# E-04_CPU_PWR.net
KiCad netlist of a schematic drawn in Altium Designer
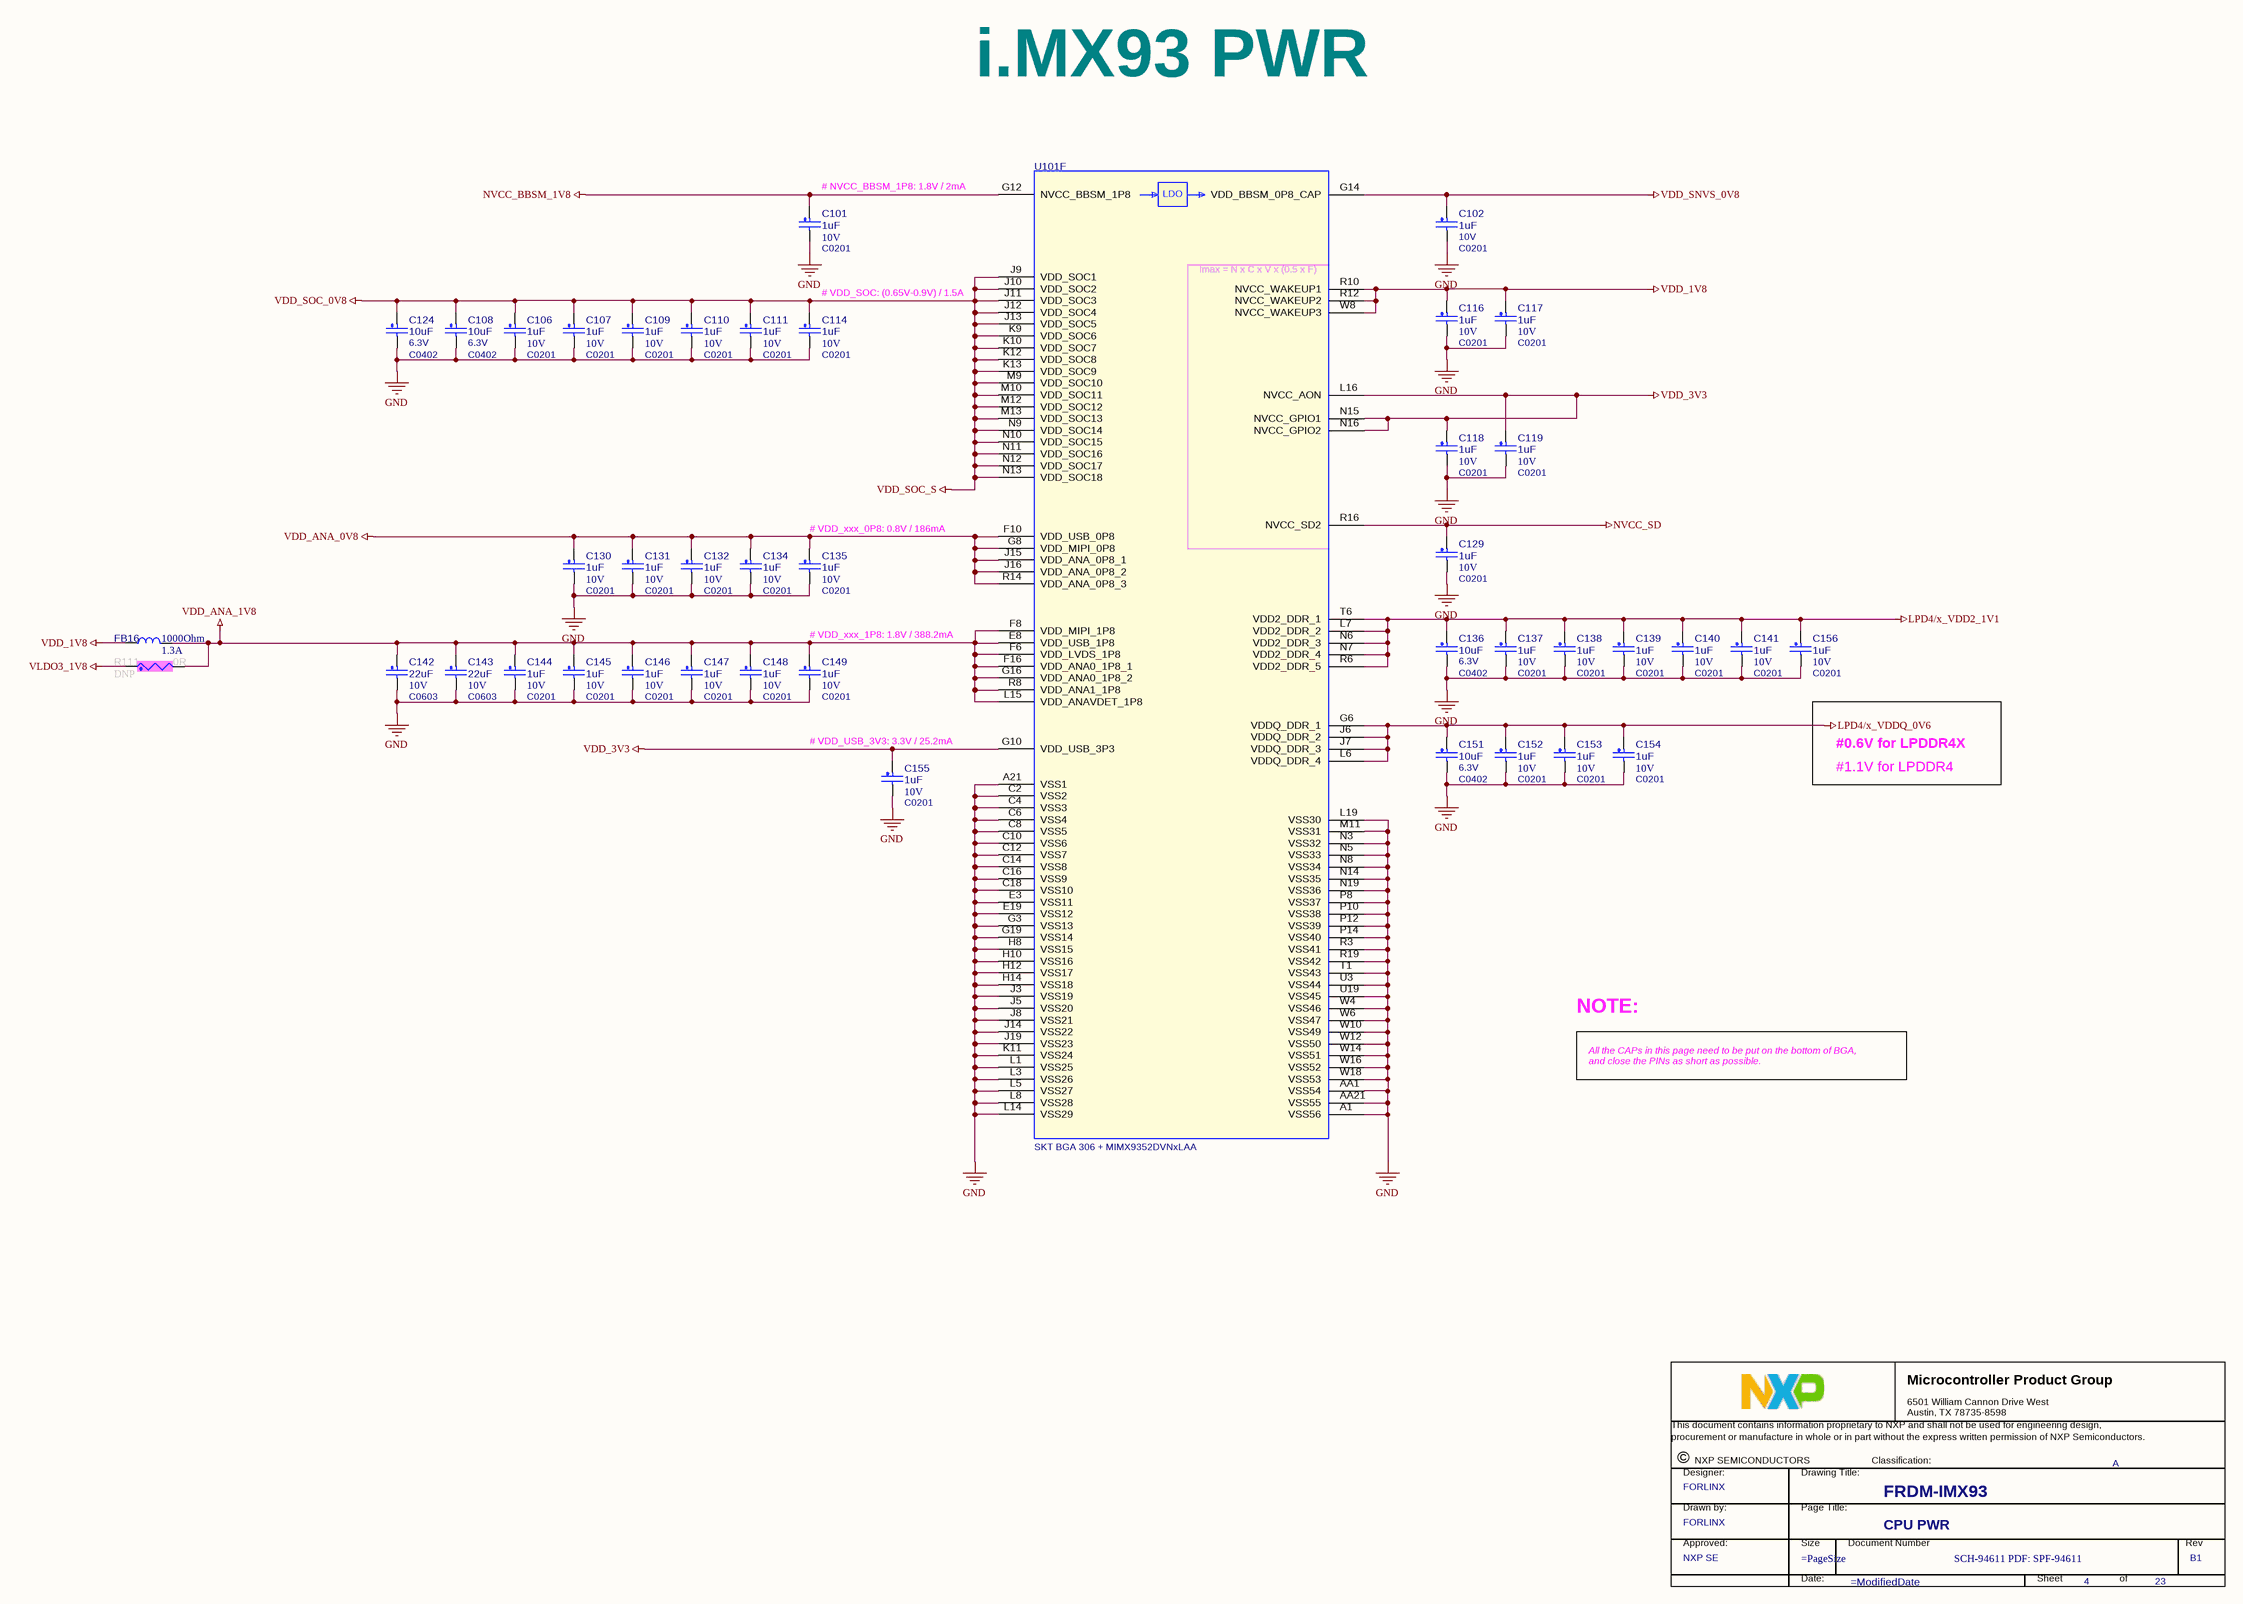
[diagram p0: E-04 CPU PWR.SchDoc]

(export (version "E")
  (design (tool "Eeschema 10.0.6"))
  (components
    (comp (ref "C101")
      (value "1uF")
      (footprint "C0201")
      (description "0201,1uF,10V,+/-20%,X5R")
      (fields
        (field (name "TOLERANCE") "10%")
        (field (name "VOLTAGE") "10V")
        (field (name "PCB FOOTPRINT") "C0201")
      )
      (libsource (lib "*") (part "CAP_NP"))
    )
    (comp (ref "C102")
      (value "1uF")
      (footprint "C0201")
      (description "0201,1uF,10V,+/-20%,X5R")
      (fields
        (field (name "VOLTAGE") "10V")
        (field (name "TOLERANCE") "20%")
        (field (name "PCB FOOTPRINT") "C0201")
      )
      (libsource (lib "*") (part "CAP_NP"))
    )
    (comp (ref "C106")
      (value "1uF")
      (footprint "C0201")
      (description "0201,1uF,10V,+/-20%,X5R")
      (fields
        (field (name "VOLTAGE") "10V")
        (field (name "TOLERANCE") "10%")
        (field (name "PCB FOOTPRINT") "C0201")
      )
      (libsource (lib "*") (part "CAP_NP"))
    )
    (comp (ref "C107")
      (value "1uF")
      (footprint "C0201")
      (description "0201,1uF,10V,+/-20%,X5R")
      (fields
        (field (name "TOLERANCE") "10%")
        (field (name "VOLTAGE") "10V")
        (field (name "PCB FOOTPRINT") "C0201")
      )
      (libsource (lib "*") (part "CAP_NP"))
    )
    (comp (ref "C108")
      (value "10uF")
      (footprint "C0402")
      (description "0402,10uF,6.3V,+/-20%,X5R")
      (fields
        (field (name "TOLERANCE") "20%")
        (field (name "VOLTAGE") "6.3V")
        (field (name "PCB FOOTPRINT") "C0402")
      )
      (libsource (lib "*") (part "CAP_NP"))
    )
    (comp (ref "C109")
      (value "1uF")
      (footprint "C0201")
      (description "0201,1uF,10V,+/-20%,X5R")
      (fields
        (field (name "TOLERANCE") "10%")
        (field (name "VOLTAGE") "10V")
        (field (name "PCB FOOTPRINT") "C0201")
      )
      (libsource (lib "*") (part "CAP_NP"))
    )
    (comp (ref "C110")
      (value "1uF")
      (footprint "C0201")
      (description "0201,1uF,10V,+/-20%,X5R")
      (fields
        (field (name "TOLERANCE") "10%")
        (field (name "VOLTAGE") "10V")
        (field (name "PCB FOOTPRINT") "C0201")
      )
      (libsource (lib "*") (part "CAP_NP"))
    )
    (comp (ref "C111")
      (value "1uF")
      (footprint "C0201")
      (description "0201,1uF,10V,+/-20%,X5R")
      (fields
        (field (name "TOLERANCE") "10%")
        (field (name "VOLTAGE") "10V")
        (field (name "PCB FOOTPRINT") "C0201")
      )
      (libsource (lib "*") (part "CAP_NP"))
    )
    (comp (ref "C114")
      (value "1uF")
      (footprint "C0201")
      (description "0201,1uF,10V,+/-20%,X5R")
      (fields
        (field (name "VOLTAGE") "10V")
        (field (name "TOLERANCE") "10%")
        (field (name "PCB FOOTPRINT") "C0201")
      )
      (libsource (lib "*") (part "CAP_NP"))
    )
    (comp (ref "C116")
      (value "1uF")
      (footprint "C0201")
      (description "0201,1uF,10V,+/-20%,X5R")
      (fields
        (field (name "VOLTAGE") "10V")
        (field (name "TOLERANCE") "10%")
        (field (name "PCB FOOTPRINT") "C0201")
      )
      (libsource (lib "*") (part "CAP_NP"))
    )
    (comp (ref "C117")
      (value "1uF")
      (footprint "C0201")
      (description "0201,1uF,10V,+/-20%,X5R")
      (fields
        (field (name "VOLTAGE") "10V")
        (field (name "TOLERANCE") "10%")
        (field (name "PCB FOOTPRINT") "C0201")
      )
      (libsource (lib "*") (part "CAP_NP"))
    )
    (comp (ref "C118")
      (value "1uF")
      (footprint "C0201")
      (description "0201,1uF,10V,+/-20%,X5R")
      (fields
        (field (name "VOLTAGE") "10V")
        (field (name "TOLERANCE") "10%")
        (field (name "PCB FOOTPRINT") "C0201")
      )
      (libsource (lib "*") (part "CAP_NP"))
    )
    (comp (ref "C119")
      (value "1uF")
      (footprint "C0201")
      (description "0201,1uF,10V,+/-20%,X5R")
      (fields
        (field (name "VOLTAGE") "10V")
        (field (name "TOLERANCE") "10%")
        (field (name "PCB FOOTPRINT") "C0201")
      )
      (libsource (lib "*") (part "CAP_NP"))
    )
    (comp (ref "C124")
      (value "10uF")
      (footprint "C0402")
      (description "0402,10uF,6.3V,+/-20%,X5R")
      (fields
        (field (name "VOLTAGE") "6.3V")
        (field (name "TOLERANCE") "20%")
        (field (name "PCB FOOTPRINT") "C0402")
      )
      (libsource (lib "*") (part "CAP_NP"))
    )
    (comp (ref "C129")
      (value "1uF")
      (footprint "C0201")
      (description "0201,1uF,10V,+/-20%,X5R")
      (fields
        (field (name "TOLERANCE") "10%")
        (field (name "VOLTAGE") "10V")
        (field (name "PCB FOOTPRINT") "C0201")
      )
      (libsource (lib "*") (part "CAP_NP"))
    )
    (comp (ref "C130")
      (value "1uF")
      (footprint "C0201")
      (description "0201,1uF,10V,+/-20%,X5R")
      (fields
        (field (name "TOLERANCE") "10%")
        (field (name "VOLTAGE") "10V")
        (field (name "PCB FOOTPRINT") "C0201")
      )
      (libsource (lib "*") (part "CAP_NP"))
    )
    (comp (ref "C131")
      (value "1uF")
      (footprint "C0201")
      (description "0201,1uF,10V,+/-20%,X5R")
      (fields
        (field (name "VOLTAGE") "10V")
        (field (name "TOLERANCE") "10%")
        (field (name "PCB FOOTPRINT") "C0201")
      )
      (libsource (lib "*") (part "CAP_NP"))
    )
    (comp (ref "C132")
      (value "1uF")
      (footprint "C0201")
      (description "0201,1uF,10V,+/-20%,X5R")
      (fields
        (field (name "VOLTAGE") "10V")
        (field (name "TOLERANCE") "10%")
        (field (name "PCB FOOTPRINT") "C0201")
      )
      (libsource (lib "*") (part "CAP_NP"))
    )
    (comp (ref "C134")
      (value "1uF")
      (footprint "C0201")
      (description "0201,1uF,10V,+/-20%,X5R")
      (fields
        (field (name "TOLERANCE") "10%")
        (field (name "VOLTAGE") "10V")
        (field (name "PCB FOOTPRINT") "C0201")
      )
      (libsource (lib "*") (part "CAP_NP"))
    )
    (comp (ref "C135")
      (value "1uF")
      (footprint "C0201")
      (description "0201,1uF,10V,+/-20%,X5R")
      (fields
        (field (name "TOLERANCE") "10%")
        (field (name "VOLTAGE") "10V")
        (field (name "PCB FOOTPRINT") "C0201")
      )
      (libsource (lib "*") (part "CAP_NP"))
    )
    (comp (ref "C136")
      (value "10uF")
      (footprint "C0402")
      (description "0402,10uF,6.3V,+/-20%,X5R")
      (fields
        (field (name "TOLERANCE") "20%")
        (field (name "VOLTAGE") "6.3V")
        (field (name "PCB FOOTPRINT") "C0402")
      )
      (libsource (lib "*") (part "CAP_NP"))
    )
    (comp (ref "C137")
      (value "1uF")
      (footprint "C0201")
      (description "0201,1uF,10V,+/-20%,X5R")
      (fields
        (field (name "TOLERANCE") "10%")
        (field (name "VOLTAGE") "10V")
        (field (name "PCB FOOTPRINT") "C0201")
      )
      (libsource (lib "*") (part "CAP_NP"))
    )
    (comp (ref "C138")
      (value "1uF")
      (footprint "C0201")
      (description "0201,1uF,10V,+/-20%,X5R")
      (fields
        (field (name "TOLERANCE") "10%")
        (field (name "VOLTAGE") "10V")
        (field (name "PCB FOOTPRINT") "C0201")
      )
      (libsource (lib "*") (part "CAP_NP"))
    )
    (comp (ref "C139")
      (value "1uF")
      (footprint "C0201")
      (description "0201,1uF,10V,+/-20%,X5R")
      (fields
        (field (name "TOLERANCE") "10%")
        (field (name "VOLTAGE") "10V")
        (field (name "PCB FOOTPRINT") "C0201")
      )
      (libsource (lib "*") (part "CAP_NP"))
    )
    (comp (ref "C140")
      (value "1uF")
      (footprint "C0201")
      (description "0201,1uF,10V,+/-20%,X5R")
      (fields
        (field (name "TOLERANCE") "10%")
        (field (name "VOLTAGE") "10V")
        (field (name "PCB FOOTPRINT") "C0201")
      )
      (libsource (lib "*") (part "CAP_NP"))
    )
    (comp (ref "C141")
      (value "1uF")
      (footprint "C0201")
      (description "0201,1uF,10V,+/-20%,X5R")
      (fields
        (field (name "TOLERANCE") "10%")
        (field (name "VOLTAGE") "10V")
        (field (name "PCB FOOTPRINT") "C0201")
      )
      (libsource (lib "*") (part "CAP_NP"))
    )
    (comp (ref "C142")
      (value "22uF")
      (footprint "C0603")
      (description "0603,22uF,6.3V,+/-20%,X5R")
      (fields
        (field (name "VOLTAGE") "10V")
        (field (name "TOLERANCE") "20%")
        (field (name "PCB FOOTPRINT") "C0603")
      )
      (libsource (lib "*") (part "CAP_NP"))
    )
    (comp (ref "C143")
      (value "22uF")
      (footprint "C0603")
      (description "0603,22uF,6.3V,+/-20%,X5R")
      (fields
        (field (name "TOLERANCE") "20%")
        (field (name "VOLTAGE") "10V")
        (field (name "PCB FOOTPRINT") "C0603")
      )
      (libsource (lib "*") (part "CAP_NP"))
    )
    (comp (ref "C144")
      (value "1uF")
      (footprint "C0201")
      (description "0201,1uF,10V,+/-20%,X5R")
      (fields
        (field (name "TOLERANCE") "10%")
        (field (name "VOLTAGE") "10V")
        (field (name "PCB FOOTPRINT") "C0201")
      )
      (libsource (lib "*") (part "CAP_NP"))
    )
    (comp (ref "C145")
      (value "1uF")
      (footprint "C0201")
      (description "0201,1uF,10V,+/-20%,X5R")
      (fields
        (field (name "VOLTAGE") "10V")
        (field (name "TOLERANCE") "10%")
        (field (name "PCB FOOTPRINT") "C0201")
      )
      (libsource (lib "*") (part "CAP_NP"))
    )
    (comp (ref "C146")
      (value "1uF")
      (footprint "C0201")
      (description "0201,1uF,10V,+/-20%,X5R")
      (fields
        (field (name "VOLTAGE") "10V")
        (field (name "TOLERANCE") "10%")
        (field (name "PCB FOOTPRINT") "C0201")
      )
      (libsource (lib "*") (part "CAP_NP"))
    )
    (comp (ref "C147")
      (value "1uF")
      (footprint "C0201")
      (description "0201,1uF,10V,+/-20%,X5R")
      (fields
        (field (name "TOLERANCE") "10%")
        (field (name "VOLTAGE") "10V")
        (field (name "PCB FOOTPRINT") "C0201")
      )
      (libsource (lib "*") (part "CAP_NP"))
    )
    (comp (ref "C148")
      (value "1uF")
      (footprint "C0201")
      (description "0201,1uF,10V,+/-20%,X5R")
      (fields
        (field (name "VOLTAGE") "10V")
        (field (name "TOLERANCE") "10%")
        (field (name "PCB FOOTPRINT") "C0201")
      )
      (libsource (lib "*") (part "CAP_NP"))
    )
    (comp (ref "C149")
      (value "1uF")
      (footprint "C0201")
      (description "0201,1uF,10V,+/-20%,X5R")
      (fields
        (field (name "TOLERANCE") "10%")
        (field (name "VOLTAGE") "10V")
        (field (name "PCB FOOTPRINT") "C0201")
      )
      (libsource (lib "*") (part "CAP_NP"))
    )
    (comp (ref "C151")
      (value "10uF")
      (footprint "C0402")
      (description "0402,10uF,6.3V,+/-20%,X5R")
      (fields
        (field (name "VOLTAGE") "6.3V")
        (field (name "TOLERANCE") "20%")
        (field (name "PCB FOOTPRINT") "C0402")
      )
      (libsource (lib "*") (part "CAP_NP"))
    )
    (comp (ref "C152")
      (value "1uF")
      (footprint "C0201")
      (description "0201,1uF,10V,+/-20%,X5R")
      (fields
        (field (name "TOLERANCE") "10%")
        (field (name "VOLTAGE") "10V")
        (field (name "PCB FOOTPRINT") "C0201")
      )
      (libsource (lib "*") (part "CAP_NP"))
    )
    (comp (ref "C153")
      (value "1uF")
      (footprint "C0201")
      (description "0201,1uF,10V,+/-20%,X5R")
      (fields
        (field (name "VOLTAGE") "10V")
        (field (name "TOLERANCE") "10%")
        (field (name "PCB FOOTPRINT") "C0201")
      )
      (libsource (lib "*") (part "CAP_NP"))
    )
    (comp (ref "C154")
      (value "1uF")
      (footprint "C0201")
      (description "0201,1uF,10V,+/-20%,X5R")
      (fields
        (field (name "VOLTAGE") "10V")
        (field (name "TOLERANCE") "10%")
        (field (name "PCB FOOTPRINT") "C0201")
      )
      (libsource (lib "*") (part "CAP_NP"))
    )
    (comp (ref "C155")
      (value "1uF")
      (footprint "C0201")
      (description "0201,1uF,10V,+/-20%,X5R")
      (fields
        (field (name "TOLERANCE") "10%")
        (field (name "VOLTAGE") "10V")
        (field (name "PCB FOOTPRINT") "C0201")
      )
      (libsource (lib "*") (part "CAP_NP"))
    )
    (comp (ref "C156")
      (value "1uF")
      (footprint "C0201")
      (description "0201,1uF,10V,+/-20%,X5R")
      (fields
        (field (name "VOLTAGE") "10V")
        (field (name "TOLERANCE") "10%")
        (field (name "PCB FOOTPRINT") "C0201")
      )
      (libsource (lib "*") (part "CAP_NP"))
    )
    (comp (ref "FB16")
      (value "1000Ohm")
      (footprint "FB0603")
      (description "0603,1000Ohm@100MHz,800mA")
      (fields (field (name "ELECTRIC CURRENT") "1.3A"))
      (libsource (lib "*") (part "FB0402,120ohm,1.3A"))
    )
    (comp (ref "R111")
      (value "0R")
      (footprint "R0603")
      (description "0603,0Ohm,+/-5%")
      (fields (field (name "ASSY_OPT") "DNP"))
      (libsource (lib "*") (part "RES"))
    )
    (comp (ref "U101")
      (value "SKT BGA 306 + MIMX9352DVNxLAA")
      (footprint "skt_bga306_0p5_sq16p23_elast_nsp")
      (description "MIMX9352CVVXMAB,-40~105+C,11*11mm,0.5mm pitch,FCBGA,A,306pin,1.7GHz")
      (libsource (lib "*") (part "MIMX9352DVNxLAA"))
    )
  )
  (nets
    (net (code "1") (name "GND") (class "Default")
      (node (ref "C101") (pin "2") (pinfunction "2_2") (pintype "passive"))
      (node (ref "C102") (pin "2") (pinfunction "2_2") (pintype "passive"))
      (node (ref "C106") (pin "2") (pinfunction "2_2") (pintype "passive"))
      (node (ref "C107") (pin "2") (pinfunction "2_2") (pintype "passive"))
      (node (ref "C108") (pin "2") (pinfunction "2_2") (pintype "passive"))
      (node (ref "C109") (pin "2") (pinfunction "2_2") (pintype "passive"))
      (node (ref "C110") (pin "2") (pinfunction "2_2") (pintype "passive"))
      (node (ref "C111") (pin "2") (pinfunction "2_2") (pintype "passive"))
      (node (ref "C114") (pin "2") (pinfunction "2_2") (pintype "passive"))
      (node (ref "C116") (pin "2") (pinfunction "2_2") (pintype "passive"))
      (node (ref "C117") (pin "2") (pinfunction "2_2") (pintype "passive"))
      (node (ref "C118") (pin "2") (pinfunction "2_2") (pintype "passive"))
      (node (ref "C119") (pin "2") (pinfunction "2_2") (pintype "passive"))
      (node (ref "C124") (pin "2") (pinfunction "2_2") (pintype "passive"))
      (node (ref "C129") (pin "2") (pinfunction "2_2") (pintype "passive"))
      (node (ref "C130") (pin "2") (pinfunction "2_2") (pintype "passive"))
      (node (ref "C131") (pin "2") (pinfunction "2_2") (pintype "passive"))
      (node (ref "C132") (pin "2") (pinfunction "2_2") (pintype "passive"))
      (node (ref "C134") (pin "2") (pinfunction "2_2") (pintype "passive"))
      (node (ref "C135") (pin "2") (pinfunction "2_2") (pintype "passive"))
      (node (ref "C136") (pin "2") (pinfunction "2_2") (pintype "passive"))
      (node (ref "C137") (pin "2") (pinfunction "2_2") (pintype "passive"))
      (node (ref "C138") (pin "2") (pinfunction "2_2") (pintype "passive"))
      (node (ref "C139") (pin "2") (pinfunction "2_2") (pintype "passive"))
      (node (ref "C140") (pin "2") (pinfunction "2_2") (pintype "passive"))
      (node (ref "C141") (pin "2") (pinfunction "2_2") (pintype "passive"))
      (node (ref "C142") (pin "2") (pinfunction "2_2") (pintype "passive"))
      (node (ref "C143") (pin "2") (pinfunction "2_2") (pintype "passive"))
      (node (ref "C144") (pin "2") (pinfunction "2_2") (pintype "passive"))
      (node (ref "C145") (pin "2") (pinfunction "2_2") (pintype "passive"))
      (node (ref "C146") (pin "2") (pinfunction "2_2") (pintype "passive"))
      (node (ref "C147") (pin "2") (pinfunction "2_2") (pintype "passive"))
      (node (ref "C148") (pin "2") (pinfunction "2_2") (pintype "passive"))
      (node (ref "C149") (pin "2") (pinfunction "2_2") (pintype "passive"))
      (node (ref "C151") (pin "2") (pinfunction "2_2") (pintype "passive"))
      (node (ref "C152") (pin "2") (pinfunction "2_2") (pintype "passive"))
      (node (ref "C153") (pin "2") (pinfunction "2_2") (pintype "passive"))
      (node (ref "C154") (pin "2") (pinfunction "2_2") (pintype "passive"))
      (node (ref "C155") (pin "2") (pinfunction "2_2") (pintype "passive"))
      (node (ref "C156") (pin "2") (pinfunction "2_2") (pintype "passive"))
      (node (ref "U101") (pin "A1") (pinfunction "VSS56_A1") (pintype "passive"))
      (node (ref "U101") (pin "A21") (pinfunction "VSS1_A21") (pintype "passive"))
      (node (ref "U101") (pin "AA1") (pinfunction "VSS54_AA1") (pintype "passive"))
      (node (ref "U101") (pin "AA21") (pinfunction "VSS55_AA21") (pintype "passive"))
      (node (ref "U101") (pin "C10") (pinfunction "VSS6_C10") (pintype "passive"))
      (node (ref "U101") (pin "C12") (pinfunction "VSS7_C12") (pintype "passive"))
      (node (ref "U101") (pin "C14") (pinfunction "VSS8_C14") (pintype "passive"))
      (node (ref "U101") (pin "C16") (pinfunction "VSS9_C16") (pintype "passive"))
      (node (ref "U101") (pin "C18") (pinfunction "VSS10_C18") (pintype "passive"))
      (node (ref "U101") (pin "C2") (pinfunction "VSS2_C2") (pintype "passive"))
      (node (ref "U101") (pin "C4") (pinfunction "VSS3_C4") (pintype "passive"))
      (node (ref "U101") (pin "C6") (pinfunction "VSS4_C6") (pintype "passive"))
      (node (ref "U101") (pin "C8") (pinfunction "VSS5_C8") (pintype "passive"))
      (node (ref "U101") (pin "E19") (pinfunction "VSS12_E19") (pintype "passive"))
      (node (ref "U101") (pin "E3") (pinfunction "VSS11_E3") (pintype "passive"))
      (node (ref "U101") (pin "G19") (pinfunction "VSS14_G19") (pintype "passive"))
      (node (ref "U101") (pin "G3") (pinfunction "VSS13_G3") (pintype "passive"))
      (node (ref "U101") (pin "H10") (pinfunction "VSS16_H10") (pintype "passive"))
      (node (ref "U101") (pin "H12") (pinfunction "VSS17_H12") (pintype "passive"))
      (node (ref "U101") (pin "H14") (pinfunction "VSS18_H14") (pintype "passive"))
      (node (ref "U101") (pin "H8") (pinfunction "VSS15_H8") (pintype "passive"))
      (node (ref "U101") (pin "J14") (pinfunction "VSS22_J14") (pintype "passive"))
      (node (ref "U101") (pin "J19") (pinfunction "VSS23_J19") (pintype "passive"))
      (node (ref "U101") (pin "J3") (pinfunction "VSS19_J3") (pintype "passive"))
      (node (ref "U101") (pin "J5") (pinfunction "VSS20_J5") (pintype "passive"))
      (node (ref "U101") (pin "J8") (pinfunction "VSS21_J8") (pintype "passive"))
      (node (ref "U101") (pin "K11") (pinfunction "VSS24_K11") (pintype "passive"))
      (node (ref "U101") (pin "L1") (pinfunction "VSS25_L1") (pintype "passive"))
      (node (ref "U101") (pin "L14") (pinfunction "VSS29_L14") (pintype "passive"))
      (node (ref "U101") (pin "L19") (pinfunction "VSS30_L19") (pintype "passive"))
      (node (ref "U101") (pin "L3") (pinfunction "VSS26_L3") (pintype "passive"))
      (node (ref "U101") (pin "L5") (pinfunction "VSS27_L5") (pintype "passive"))
      (node (ref "U101") (pin "L8") (pinfunction "VSS28_L8") (pintype "passive"))
      (node (ref "U101") (pin "M11") (pinfunction "VSS31_M11") (pintype "passive"))
      (node (ref "U101") (pin "N14") (pinfunction "VSS35_N14") (pintype "passive"))
      (node (ref "U101") (pin "N19") (pinfunction "VSS36_N19") (pintype "passive"))
      (node (ref "U101") (pin "N3") (pinfunction "VSS32_N3") (pintype "passive"))
      (node (ref "U101") (pin "N5") (pinfunction "VSS33_N5") (pintype "passive"))
      (node (ref "U101") (pin "N8") (pinfunction "VSS34_N8") (pintype "passive"))
      (node (ref "U101") (pin "P10") (pinfunction "VSS38_P10") (pintype "passive"))
      (node (ref "U101") (pin "P12") (pinfunction "VSS39_P12") (pintype "passive"))
      (node (ref "U101") (pin "P14") (pinfunction "VSS40_P14") (pintype "passive"))
      (node (ref "U101") (pin "P8") (pinfunction "VSS37_P8") (pintype "passive"))
      (node (ref "U101") (pin "R19") (pinfunction "VSS42_R19") (pintype "passive"))
      (node (ref "U101") (pin "R3") (pinfunction "VSS41_R3") (pintype "passive"))
      (node (ref "U101") (pin "T1") (pinfunction "VSS43_T1") (pintype "passive"))
      (node (ref "U101") (pin "U19") (pinfunction "VSS45_U19") (pintype "passive"))
      (node (ref "U101") (pin "U3") (pinfunction "VSS44_U3") (pintype "passive"))
      (node (ref "U101") (pin "W10") (pinfunction "VSS49_W10") (pintype "passive"))
      (node (ref "U101") (pin "W12") (pinfunction "VSS50_W12") (pintype "passive"))
      (node (ref "U101") (pin "W14") (pinfunction "VSS51_W14") (pintype "passive"))
      (node (ref "U101") (pin "W16") (pinfunction "VSS52_W16") (pintype "passive"))
      (node (ref "U101") (pin "W18") (pinfunction "VSS53_W18") (pintype "passive"))
      (node (ref "U101") (pin "W4") (pinfunction "VSS46_W4") (pintype "passive"))
      (node (ref "U101") (pin "W6") (pinfunction "VSS47_W6") (pintype "passive"))
    )
    (net (code "2") (name "LPD4{slash}x_VDD2_1V1") (class "Default")
      (node (ref "C136") (pin "1") (pinfunction "1_1") (pintype "passive"))
      (node (ref "C137") (pin "1") (pinfunction "1_1") (pintype "passive"))
      (node (ref "C138") (pin "1") (pinfunction "1_1") (pintype "passive"))
      (node (ref "C139") (pin "1") (pinfunction "1_1") (pintype "passive"))
      (node (ref "C140") (pin "1") (pinfunction "1_1") (pintype "passive"))
      (node (ref "C141") (pin "1") (pinfunction "1_1") (pintype "passive"))
      (node (ref "C156") (pin "1") (pinfunction "1_1") (pintype "passive"))
      (node (ref "U101") (pin "L7") (pinfunction "VDD2_DDR_2_L7") (pintype "passive"))
      (node (ref "U101") (pin "N6") (pinfunction "VDD2_DDR_3_N6") (pintype "passive"))
      (node (ref "U101") (pin "N7") (pinfunction "VDD2_DDR_4_N7") (pintype "passive"))
      (node (ref "U101") (pin "R6") (pinfunction "VDD2_DDR_5_R6") (pintype "passive"))
      (node (ref "U101") (pin "T6") (pinfunction "VDD2_DDR_1_T6") (pintype "passive"))
    )
    (net (code "3") (name "LPD4{slash}x_VDDQ_0V6") (class "Default")
      (node (ref "C151") (pin "1") (pinfunction "1_1") (pintype "passive"))
      (node (ref "C152") (pin "1") (pinfunction "1_1") (pintype "passive"))
      (node (ref "C153") (pin "1") (pinfunction "1_1") (pintype "passive"))
      (node (ref "C154") (pin "1") (pinfunction "1_1") (pintype "passive"))
      (node (ref "U101") (pin "G6") (pinfunction "VDDQ_DDR_1_G6") (pintype "passive"))
      (node (ref "U101") (pin "J6") (pinfunction "VDDQ_DDR_2_J6") (pintype "passive"))
      (node (ref "U101") (pin "J7") (pinfunction "VDDQ_DDR_3_J7") (pintype "passive"))
      (node (ref "U101") (pin "L6") (pinfunction "VDDQ_DDR_4_L6") (pintype "passive"))
    )
    (net (code "4") (name "NVCC_BBSM_1V8") (class "Default")
      (node (ref "C101") (pin "1") (pinfunction "1_1") (pintype "passive"))
      (node (ref "U101") (pin "G12") (pinfunction "NVCC_BBSM_1P8_G12") (pintype "passive"))
    )
    (net (code "5") (name "NVCC_SD") (class "Default")
      (node (ref "C129") (pin "1") (pinfunction "1_1") (pintype "passive"))
      (node (ref "U101") (pin "R16") (pinfunction "NVCC_SD2_R16") (pintype "passive"))
    )
    (net (code "6") (name "VDD_1V8") (class "Default")
      (node (ref "C116") (pin "1") (pinfunction "1_1") (pintype "passive"))
      (node (ref "C117") (pin "1") (pinfunction "1_1") (pintype "passive"))
      (node (ref "FB16") (pin "1") (pinfunction "1_1") (pintype "passive"))
      (node (ref "U101") (pin "R10") (pinfunction "NVCC_WAKEUP1_R10") (pintype "passive"))
      (node (ref "U101") (pin "R12") (pinfunction "NVCC_WAKEUP2_R12") (pintype "passive"))
      (node (ref "U101") (pin "W8") (pinfunction "NVCC_WAKEUP3_W8") (pintype "passive"))
    )
    (net (code "7") (name "VDD_3V3") (class "Default")
      (node (ref "C118") (pin "1") (pinfunction "1_1") (pintype "passive"))
      (node (ref "C119") (pin "1") (pinfunction "1_1") (pintype "passive"))
      (node (ref "C155") (pin "1") (pinfunction "1_1") (pintype "passive"))
      (node (ref "U101") (pin "G10") (pinfunction "VDD_USB_3P3_G10") (pintype "passive"))
      (node (ref "U101") (pin "L16") (pinfunction "NVCC_AON_L16") (pintype "passive"))
      (node (ref "U101") (pin "N15") (pinfunction "NVCC_GPIO1_N15") (pintype "passive"))
      (node (ref "U101") (pin "N16") (pinfunction "NVCC_GPIO2_N16") (pintype "passive"))
    )
    (net (code "8") (name "VDD_ANA_0V8") (class "Default")
      (node (ref "C130") (pin "1") (pinfunction "1_1") (pintype "passive"))
      (node (ref "C131") (pin "1") (pinfunction "1_1") (pintype "passive"))
      (node (ref "C132") (pin "1") (pinfunction "1_1") (pintype "passive"))
      (node (ref "C134") (pin "1") (pinfunction "1_1") (pintype "passive"))
      (node (ref "C135") (pin "1") (pinfunction "1_1") (pintype "passive"))
      (node (ref "U101") (pin "F10") (pinfunction "VDD_USB_0P8_F10") (pintype "passive"))
      (node (ref "U101") (pin "G8") (pinfunction "VDD_MIPI_0P8_G8") (pintype "passive"))
      (node (ref "U101") (pin "J15") (pinfunction "VDD_ANA_0P8_1_J15") (pintype "passive"))
      (node (ref "U101") (pin "J16") (pinfunction "VDD_ANA_0P8_2_J16") (pintype "passive"))
      (node (ref "U101") (pin "R14") (pinfunction "VDD_ANA_0P8_3_R14") (pintype "passive"))
    )
    (net (code "9") (name "VDD_ANA_1V8") (class "Default")
      (node (ref "C142") (pin "1") (pinfunction "1_1") (pintype "passive"))
      (node (ref "C143") (pin "1") (pinfunction "1_1") (pintype "passive"))
      (node (ref "C144") (pin "1") (pinfunction "1_1") (pintype "passive"))
      (node (ref "C145") (pin "1") (pinfunction "1_1") (pintype "passive"))
      (node (ref "C146") (pin "1") (pinfunction "1_1") (pintype "passive"))
      (node (ref "C147") (pin "1") (pinfunction "1_1") (pintype "passive"))
      (node (ref "C148") (pin "1") (pinfunction "1_1") (pintype "passive"))
      (node (ref "C149") (pin "1") (pinfunction "1_1") (pintype "passive"))
      (node (ref "FB16") (pin "2") (pinfunction "2_2") (pintype "passive"))
      (node (ref "R111") (pin "2") (pinfunction "2_2") (pintype "passive"))
      (node (ref "U101") (pin "E8") (pinfunction "VDD_USB_1P8_E8") (pintype "passive"))
      (node (ref "U101") (pin "F16") (pinfunction "VDD_ANA0_1P8_1_F16") (pintype "passive"))
      (node (ref "U101") (pin "F6") (pinfunction "VDD_LVDS_1P8_F6") (pintype "passive"))
      (node (ref "U101") (pin "F8") (pinfunction "VDD_MIPI_1P8_F8") (pintype "passive"))
      (node (ref "U101") (pin "G16") (pinfunction "VDD_ANA0_1P8_2_G16") (pintype "passive"))
      (node (ref "U101") (pin "L15") (pinfunction "VDD_ANAVDET_1P8_L15") (pintype "passive"))
      (node (ref "U101") (pin "R8") (pinfunction "VDD_ANA1_1P8_R8") (pintype "passive"))
    )
    (net (code "10") (name "VDD_SNVS_0V8") (class "Default")
      (node (ref "C102") (pin "1") (pinfunction "1_1") (pintype "passive"))
      (node (ref "U101") (pin "G14") (pinfunction "VDD_BBSM_0P8_CAP_G14") (pintype "passive"))
    )
    (net (code "11") (name "VDD_SOC_0V8") (class "Default")
      (node (ref "C106") (pin "1") (pinfunction "1_1") (pintype "passive"))
      (node (ref "C107") (pin "1") (pinfunction "1_1") (pintype "passive"))
      (node (ref "C108") (pin "1") (pinfunction "1_1") (pintype "passive"))
      (node (ref "C109") (pin "1") (pinfunction "1_1") (pintype "passive"))
      (node (ref "C110") (pin "1") (pinfunction "1_1") (pintype "passive"))
      (node (ref "C111") (pin "1") (pinfunction "1_1") (pintype "passive"))
      (node (ref "C114") (pin "1") (pinfunction "1_1") (pintype "passive"))
      (node (ref "C124") (pin "1") (pinfunction "1_1") (pintype "passive"))
      (node (ref "U101") (pin "J10") (pinfunction "VDD_SOC2_J10") (pintype "passive"))
      (node (ref "U101") (pin "J11") (pinfunction "VDD_SOC3_J11") (pintype "passive"))
      (node (ref "U101") (pin "J12") (pinfunction "VDD_SOC4_J12") (pintype "passive"))
      (node (ref "U101") (pin "J13") (pinfunction "VDD_SOC5_J13") (pintype "passive"))
      (node (ref "U101") (pin "J9") (pinfunction "VDD_SOC1_J9") (pintype "passive"))
      (node (ref "U101") (pin "K10") (pinfunction "VDD_SOC7_K10") (pintype "passive"))
      (node (ref "U101") (pin "K12") (pinfunction "VDD_SOC8_K12") (pintype "passive"))
      (node (ref "U101") (pin "K13") (pinfunction "VDD_SOC9_K13") (pintype "passive"))
      (node (ref "U101") (pin "K9") (pinfunction "VDD_SOC6_K9") (pintype "passive"))
      (node (ref "U101") (pin "M10") (pinfunction "VDD_SOC11_M10") (pintype "passive"))
      (node (ref "U101") (pin "M12") (pinfunction "VDD_SOC12_M12") (pintype "passive"))
      (node (ref "U101") (pin "M13") (pinfunction "VDD_SOC13_M13") (pintype "passive"))
      (node (ref "U101") (pin "M9") (pinfunction "VDD_SOC10_M9") (pintype "passive"))
      (node (ref "U101") (pin "N10") (pinfunction "VDD_SOC15_N10") (pintype "passive"))
      (node (ref "U101") (pin "N11") (pinfunction "VDD_SOC16_N11") (pintype "passive"))
      (node (ref "U101") (pin "N12") (pinfunction "VDD_SOC17_N12") (pintype "passive"))
      (node (ref "U101") (pin "N13") (pinfunction "VDD_SOC18_N13") (pintype "passive"))
      (node (ref "U101") (pin "N9") (pinfunction "VDD_SOC14_N9") (pintype "passive"))
    )
    (net (code "12") (name "VLDO3_1V8") (class "Default")
      (node (ref "R111") (pin "1") (pinfunction "1_1") (pintype "passive"))
    )
  )
)
